# fororder.net
KiCad netlist of a schematic drawn in Altium Designer
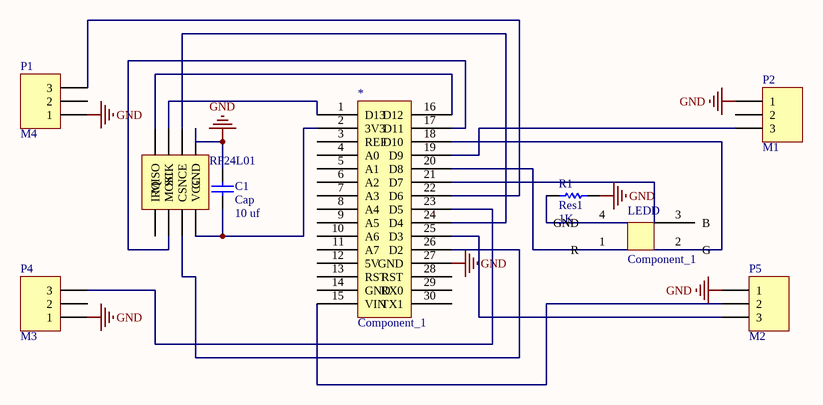
[diagram p0: fororder.SchDoc]

(export (version "E")
  (design (tool "Eeschema 10.0.6"))
  (components
    (comp (ref "*")
      (value "Component_1")
      (footprint "PCBComponent_1")
      (libsource (lib "Schlib2") (part "Component_1"))
    )
    (comp (ref "C1")
      (value "Cap")
      (footprint "RAD-0.1")
      (description "Capacitor")
      (fields (field (name "ALTIUM_VALUE") "10 uf") (field (name "PUBLISHER") "Altium Limited"))
      (libsource (lib "Miscellaneous Devices") (part "Cap"))
    )
    (comp (ref "LED")
      (value "Component_1")
      (footprint "LED")
      (libsource (lib "Schlib1") (part "Component_1"))
    )
    (comp (ref "P1")
      (value "M4")
      (footprint "HDR1X3")
      (description "Header, 3-Pin")
      (fields (field (name "PUBLISHER") "Altium Limited"))
      (libsource (lib "Miscellaneous Connectors") (part "Header 3"))
    )
    (comp (ref "P2")
      (value "M1")
      (footprint "HDR1X3")
      (description "Header, 3-Pin")
      (fields (field (name "PUBLISHER") "Altium Limited"))
      (libsource (lib "") (part "Header 3_1"))
    )
    (comp (ref "P4")
      (value "M3")
      (footprint "HDR1X3")
      (description "Header, 3-Pin")
      (fields (field (name "PUBLISHER") "Altium Limited"))
      (libsource (lib "Miscellaneous Connectors") (part "Header 3"))
    )
    (comp (ref "P5")
      (value "M2")
      (footprint "HDR1X3")
      (description "Header, 3-Pin")
      (fields (field (name "PUBLISHER") "Altium Limited"))
      (libsource (lib "") (part "Header 3_1"))
    )
    (comp (ref "R1")
      (value "Res1")
      (footprint "AXIAL-0.3")
      (description "Resistor")
      (fields (field (name "ALTIUM_VALUE") "1K") (field (name "PUBLISHER") "Altium Limited"))
      (libsource (lib "Miscellaneous Devices") (part "Res1"))
    )
    (comp (ref "RF24L01")
      (value "Header 4X2H")
      (footprint "HDR2X4H")
      (description "Header, 4-Pin, Dual row, Right Angle")
      (fields (field (name "PUBLISHER") "Altium Limited"))
      (libsource (lib "Miscellaneous Connectors") (part "Header 4X2H"))
    )
  )
  (nets
    (net (code "1") (name "GND") (class "Default")
      (node (ref "*") (pin "27") (pinfunction "GND_27") (pintype "passive"))
      (node (ref "C1") (pin "1") (pinfunction "1_1") (pintype "passive"))
      (node (ref "P1") (pin "1") (pinfunction "1_1") (pintype "passive"))
      (node (ref "P2") (pin "1") (pinfunction "1_1") (pintype "passive"))
      (node (ref "P4") (pin "1") (pinfunction "1_1") (pintype "passive"))
      (node (ref "P5") (pin "1") (pinfunction "1_1") (pintype "passive"))
      (node (ref "R1") (pin "2") (pinfunction "2_2") (pintype "passive"))
      (node (ref "RF24L01") (pin "1") (pinfunction "GND_1") (pintype "passive"))
    )
    (net (code "2") (name "Net-(*-3V3)") (class "Default")
      (node (ref "*") (pin "2") (pinfunction "3V3_2") (pintype "passive"))
      (node (ref "C1") (pin "2") (pinfunction "2_2") (pintype "passive"))
      (node (ref "RF24L01") (pin "2") (pinfunction "VCC_2") (pintype "passive"))
    )
    (net (code "3") (name "Net-(*-D2)") (class "Default")
      (node (ref "*") (pin "26") (pinfunction "D2_26") (pintype "passive"))
      (node (ref "RF24L01") (pin "4") (pinfunction "CSN_4") (pintype "passive"))
    )
    (net (code "4") (name "Net-(*-D3)") (class "Default")
      (node (ref "*") (pin "25") (pinfunction "D3_25") (pintype "passive"))
      (node (ref "P5") (pin "3") (pinfunction "3_3") (pintype "passive"))
    )
    (net (code "5") (name "Net-(*-D4)") (class "Default")
      (node (ref "*") (pin "24") (pinfunction "D4_24") (pintype "passive"))
      (node (ref "RF24L01") (pin "3") (pinfunction "CE_3") (pintype "passive"))
    )
    (net (code "6") (name "Net-(*-D5)") (class "Default")
      (node (ref "*") (pin "23") (pinfunction "D5_23") (pintype "passive"))
      (node (ref "P4") (pin "3") (pinfunction "3_3") (pintype "passive"))
    )
    (net (code "7") (name "Net-(*-D6)") (class "Default")
      (node (ref "*") (pin "22") (pinfunction "D6_22") (pintype "passive"))
      (node (ref "P1") (pin "3") (pinfunction "3_3") (pintype "passive"))
    )
    (net (code "8") (name "Net-(*-D7)") (class "Default")
      (node (ref "*") (pin "21") (pinfunction "D7_21") (pintype "passive"))
      (node (ref "LED") (pin "3") (pinfunction "B_3") (pintype "passive"))
    )
    (net (code "9") (name "Net-(*-D8)") (class "Default")
      (node (ref "*") (pin "20") (pinfunction "D8_20") (pintype "passive"))
      (node (ref "LED") (pin "1") (pinfunction "R_1") (pintype "passive"))
    )
    (net (code "10") (name "Net-(*-D9)") (class "Default")
      (node (ref "*") (pin "19") (pinfunction "D9_19") (pintype "passive"))
      (node (ref "P2") (pin "3") (pinfunction "3_3") (pintype "passive"))
    )
    (net (code "11") (name "Net-(*-D10)") (class "Default")
      (node (ref "*") (pin "18") (pinfunction "D10_18") (pintype "passive"))
      (node (ref "LED") (pin "2") (pinfunction "G_2") (pintype "passive"))
    )
    (net (code "12") (name "Net-(*-D11)") (class "Default")
      (node (ref "*") (pin "17") (pinfunction "D11_17") (pintype "passive"))
      (node (ref "RF24L01") (pin "6") (pinfunction "MOSI_6") (pintype "passive"))
    )
    (net (code "13") (name "Net-(*-D12)") (class "Default")
      (node (ref "*") (pin "16") (pinfunction "D12_16") (pintype "passive"))
      (node (ref "RF24L01") (pin "7") (pinfunction "MISO_7") (pintype "passive"))
    )
    (net (code "14") (name "Net-(*-D13)") (class "Default")
      (node (ref "*") (pin "1") (pinfunction "D13_1") (pintype "passive"))
      (node (ref "RF24L01") (pin "5") (pinfunction "SCK_5") (pintype "passive"))
    )
    (net (code "15") (name "Net-(*-VIN)") (class "Default")
      (node (ref "*") (pin "15") (pinfunction "VIN_15") (pintype "passive"))
      (node (ref "P5") (pin "2") (pinfunction "2_2") (pintype "passive"))
    )
    (net (code "16") (name "Net-(LEDD-GND)") (class "Default")
      (node (ref "LED") (pin "4") (pinfunction "GND_4") (pintype "passive"))
      (node (ref "R1") (pin "1") (pinfunction "1_1") (pintype "passive"))
    )
    (net (code "17") (name "unconnected-(*-5V-Pad12)") (class "Default")
      (node (ref "*") (pin "12") (pinfunction "5V_12") (pintype "passive"))
    )
    (net (code "18") (name "unconnected-(*-A0-Pad4)") (class "Default")
      (node (ref "*") (pin "4") (pinfunction "A0_4") (pintype "passive"))
    )
    (net (code "19") (name "unconnected-(*-A1-Pad5)") (class "Default")
      (node (ref "*") (pin "5") (pinfunction "A1_5") (pintype "passive"))
    )
    (net (code "20") (name "unconnected-(*-A2-Pad6)") (class "Default")
      (node (ref "*") (pin "6") (pinfunction "A2_6") (pintype "passive"))
    )
    (net (code "21") (name "unconnected-(*-A3-Pad7)") (class "Default")
      (node (ref "*") (pin "7") (pinfunction "A3_7") (pintype "passive"))
    )
    (net (code "22") (name "unconnected-(*-A4-Pad8)") (class "Default")
      (node (ref "*") (pin "8") (pinfunction "A4_8") (pintype "passive"))
    )
    (net (code "23") (name "unconnected-(*-A5-Pad9)") (class "Default")
      (node (ref "*") (pin "9") (pinfunction "A5_9") (pintype "passive"))
    )
    (net (code "24") (name "unconnected-(*-A6-Pad10)") (class "Default")
      (node (ref "*") (pin "10") (pinfunction "A6_10") (pintype "passive"))
    )
    (net (code "25") (name "unconnected-(*-A7-Pad11)") (class "Default")
      (node (ref "*") (pin "11") (pinfunction "A7_11") (pintype "passive"))
    )
    (net (code "26") (name "unconnected-(*-GND-Pad14)") (class "Default")
      (node (ref "*") (pin "14") (pinfunction "GND_14") (pintype "passive"))
    )
    (net (code "27") (name "unconnected-(*-REF-Pad3)") (class "Default")
      (node (ref "*") (pin "3") (pinfunction "REF_3") (pintype "passive"))
    )
    (net (code "28") (name "unconnected-(*-RST-Pad13)") (class "Default")
      (node (ref "*") (pin "13") (pinfunction "RST_13") (pintype "passive"))
    )
    (net (code "29") (name "unconnected-(*-RST-Pad28)") (class "Default")
      (node (ref "*") (pin "28") (pinfunction "RST_28") (pintype "passive"))
    )
    (net (code "30") (name "unconnected-(*-RX0-Pad29)") (class "Default")
      (node (ref "*") (pin "29") (pinfunction "RX0_29") (pintype "passive"))
    )
    (net (code "31") (name "unconnected-(*-TX1-Pad30)") (class "Default")
      (node (ref "*") (pin "30") (pinfunction "TX1_30") (pintype "passive"))
    )
    (net (code "32") (name "unconnected-(P1-Pad2)") (class "Default")
      (node (ref "P1") (pin "2") (pinfunction "2_2") (pintype "passive"))
    )
    (net (code "33") (name "unconnected-(P2-Pad2)") (class "Default")
      (node (ref "P2") (pin "2") (pinfunction "2_2") (pintype "passive"))
    )
    (net (code "34") (name "unconnected-(P4-Pad2)") (class "Default")
      (node (ref "P4") (pin "2") (pinfunction "2_2") (pintype "passive"))
    )
    (net (code "35") (name "unconnected-(RF24L01-IRQ-Pad8)") (class "Default")
      (node (ref "RF24L01") (pin "8") (pinfunction "IRQ_8") (pintype "passive"))
    )
  )
)
